# esp8266Board.net
KiCad netlist of a schematic drawn in EAGLE
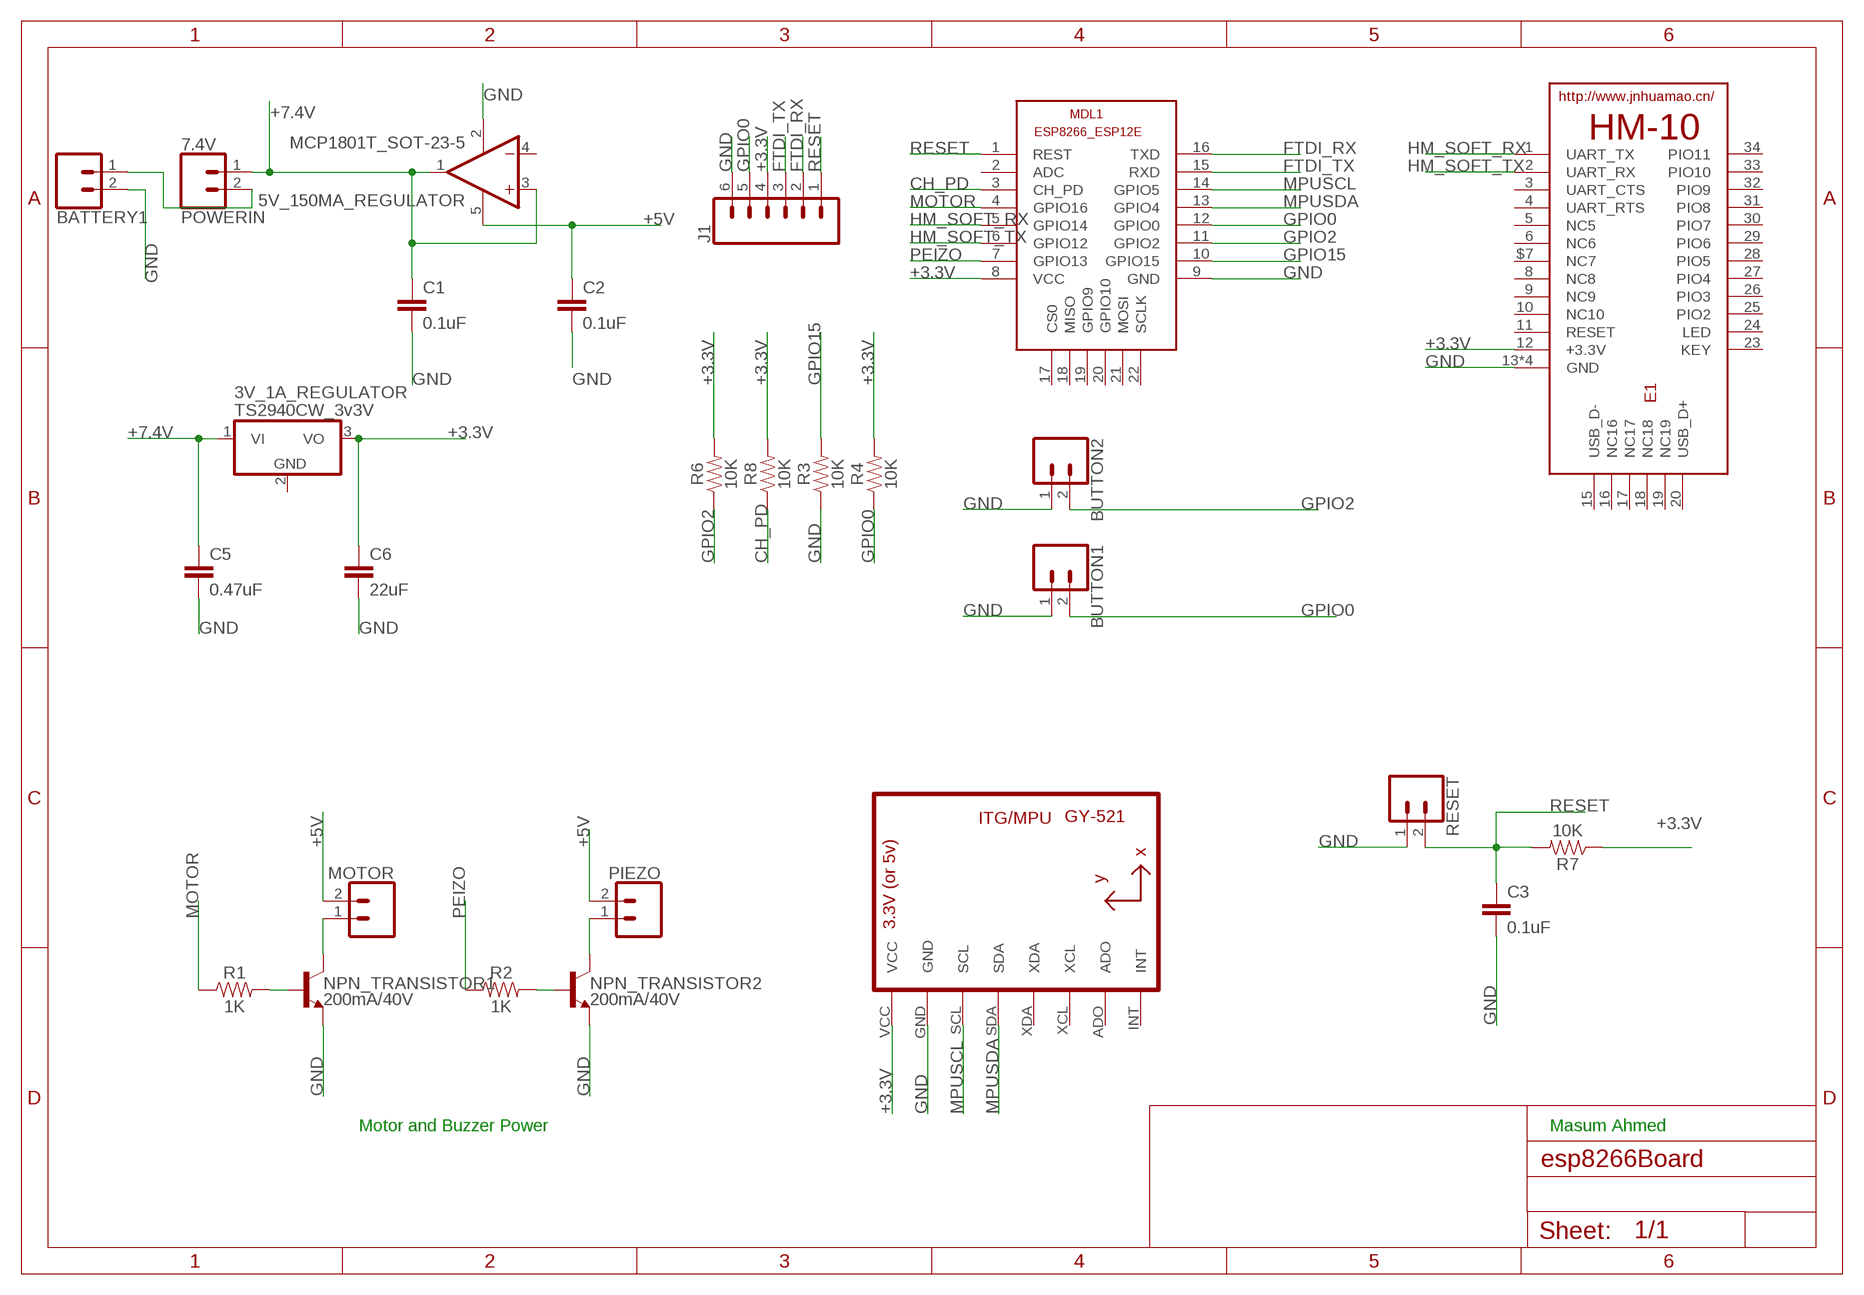
[diagram p0: schematic, sheet 1]

(export (version "E")
  (design (tool "Eeschema 10.0.6"))
  (components
    (comp (ref "3V_1A_REGULATOR")
      (value "TS2940CW_3v3V")
      (footprint "eagle-import:SOT223")
      (libsource (lib "eagle-import") (part "MCP1703DB"))
    )
    (comp (ref "5V_150MA_REGULATOR")
      (value "MCP1801T_SOT-23-5")
      (footprint "eagle-import:SOT23-5")
      (libsource (lib "eagle-import") (part "MCP601OT"))
    )
    (comp (ref "BATTERY1")
      (value "CONN_02")
      (footprint "eagle-import:1X02")
      (libsource (lib "eagle-import") (part "CONN_02"))
    )
    (comp (ref "BUTTON1")
      (value "CONN_02")
      (footprint "eagle-import:1X02")
      (libsource (lib "eagle-import") (part "CONN_02"))
    )
    (comp (ref "BUTTON2")
      (value "CONN_02")
      (footprint "eagle-import:1X02")
      (libsource (lib "eagle-import") (part "CONN_02"))
    )
    (comp (ref "C1")
      (value "0.1uF")
      (footprint "eagle-import:0805")
      (libsource (lib "eagle-import") (part "1.0UF-0805-25V-10%"))
    )
    (comp (ref "C2")
      (value "0.1uF")
      (footprint "eagle-import:0805")
      (libsource (lib "eagle-import") (part "1.0UF-0805-25V-10%"))
    )
    (comp (ref "C3")
      (value "0.1uF")
      (footprint "eagle-import:0805")
      (libsource (lib "eagle-import") (part "1.0UF-0805-25V-10%"))
    )
    (comp (ref "C5")
      (value "0.47uF")
      (footprint "eagle-import:CAP-PTH-SMALL-KIT")
      (libsource (lib "eagle-import") (part "0.1UF-KIT-EZ-50V-20%"))
    )
    (comp (ref "C6")
      (value "22uF")
      (footprint "eagle-import:CAP-PTH-SMALL-KIT")
      (libsource (lib "eagle-import") (part "0.1UF-KIT-EZ-50V-20%"))
    )
    (comp (ref "E1")
      (value "HM-10-BOARD")
      (footprint "eagle-import:26.9X13X2.2_BOARD")
      (libsource (lib "eagle-import") (part "HM-10-BOARD"))
    )
    (comp (ref "J1")
      (value "CONN_06SILK_FEMALE_PTH")
      (footprint "eagle-import:1X06")
      (libsource (lib "eagle-import") (part "CONN_06SILK_FEMALE_PTH"))
    )
    (comp (ref "MDL1")
      (value "ESP8266-12EESP8266-ESP12E")
      (footprint "eagle-import:ESP8266-ESP12E")
      (libsource (lib "eagle-import") (part "ESP8266-12EESP8266-ESP12E"))
    )
    (comp (ref "MOTOR")
      (value "CONN_02")
      (footprint "eagle-import:1X02")
      (libsource (lib "eagle-import") (part "CONN_02"))
    )
    (comp (ref "NPN_TRANSISTOR1")
      (value "200mA/40V")
      (footprint "eagle-import:TO-92")
      (libsource (lib "eagle-import") (part "TRANS_NPN-2N3904"))
    )
    (comp (ref "NPN_TRANSISTOR2")
      (value "200mA/40V")
      (footprint "eagle-import:TO-92")
      (libsource (lib "eagle-import") (part "TRANS_NPN-2N3904"))
    )
    (comp (ref "PIEZO")
      (value "CONN_02")
      (footprint "eagle-import:1X02")
      (libsource (lib "eagle-import") (part "CONN_02"))
    )
    (comp (ref "POWERIN")
      (value "7.4V")
      (footprint "eagle-import:1X02")
      (libsource (lib "eagle-import") (part "CONN_02"))
    )
    (comp (ref "R1")
      (value "1K")
      (footprint "eagle-import:0805")
      (libsource (lib "eagle-import") (part "0.22OHM-0805-1/4W-1%"))
    )
    (comp (ref "R2")
      (value "1K")
      (footprint "eagle-import:0805")
      (libsource (lib "eagle-import") (part "0.22OHM-0805-1/4W-1%"))
    )
    (comp (ref "R3")
      (value "10K")
      (footprint "eagle-import:0805")
      (libsource (lib "eagle-import") (part "0.22OHM-0805-1/4W-1%"))
    )
    (comp (ref "R4")
      (value "10K")
      (footprint "eagle-import:0805")
      (libsource (lib "eagle-import") (part "0.22OHM-0805-1/4W-1%"))
    )
    (comp (ref "R6")
      (value "10K")
      (footprint "eagle-import:0805")
      (libsource (lib "eagle-import") (part "0.22OHM-0805-1/4W-1%"))
    )
    (comp (ref "R7")
      (value "10K")
      (footprint "eagle-import:0805")
      (libsource (lib "eagle-import") (part "0.22OHM-0805-1/4W-1%"))
    )
    (comp (ref "R8")
      (value "10K")
      (footprint "eagle-import:0805")
      (libsource (lib "eagle-import") (part "0.22OHM-0805-1/4W-1%"))
    )
    (comp (ref "RESET")
      (value "CONN_02")
      (footprint "eagle-import:1X02")
      (libsource (lib "eagle-import") (part "CONN_02"))
    )
    (comp (ref "U1")
      (value "GY-521MPU6050")
      (footprint "eagle-import:GY-521")
      (libsource (lib "eagle-import") (part "GY-521MPU6050"))
    )
  )
  (nets
    (net (code "1") (name "/+3.3V") (class "Default")
      (node (ref "3V_1A_REGULATOR") (pin "3") (pinfunction "VO_3") (pintype "passive"))
      (node (ref "C6") (pin "1") (pinfunction "1_1") (pintype "passive"))
      (node (ref "E1") (pin "12") (pinfunction "+3.3V_12") (pintype "bidirectional"))
      (node (ref "J1") (pin "4") (pinfunction "4_4") (pintype "passive"))
      (node (ref "MDL1") (pin "8") (pinfunction "VCC_8") (pintype "bidirectional"))
      (node (ref "R4") (pin "2") (pinfunction "2_2") (pintype "passive"))
      (node (ref "R6") (pin "2") (pinfunction "2_2") (pintype "passive"))
      (node (ref "R7") (pin "1") (pinfunction "1_1") (pintype "passive"))
      (node (ref "R8") (pin "2") (pinfunction "2_2") (pintype "passive"))
      (node (ref "U1") (pin "VCC") (pinfunction "VCC_VCC") (pintype "bidirectional"))
    )
    (net (code "2") (name "/+5V") (class "Default")
      (node (ref "5V_150MA_REGULATOR") (pin "5") (pinfunction "V+_5") (pintype "power_in"))
      (node (ref "C2") (pin "1") (pinfunction "1_1") (pintype "passive"))
      (node (ref "MOTOR") (pin "2") (pinfunction "2_2") (pintype "passive"))
      (node (ref "PIEZO") (pin "2") (pinfunction "2_2") (pintype "passive"))
    )
    (net (code "3") (name "/+7.4V") (class "Default")
      (node (ref "3V_1A_REGULATOR") (pin "1") (pinfunction "VI_1") (pintype "input"))
      (node (ref "5V_150MA_REGULATOR") (pin "1") (pinfunction "OUT_1") (pintype "output"))
      (node (ref "5V_150MA_REGULATOR") (pin "3") (pinfunction "+IN_3") (pintype "input"))
      (node (ref "C1") (pin "1") (pinfunction "1_1") (pintype "passive"))
      (node (ref "C5") (pin "1") (pinfunction "1_1") (pintype "passive"))
      (node (ref "POWERIN") (pin "1") (pinfunction "1_1") (pintype "passive"))
    )
    (net (code "4") (name "/CH_PD") (class "Default")
      (node (ref "MDL1") (pin "3") (pinfunction "CH_PD_3") (pintype "bidirectional"))
      (node (ref "R8") (pin "1") (pinfunction "1_1") (pintype "passive"))
    )
    (net (code "5") (name "/FTDI_RX") (class "Default")
      (node (ref "J1") (pin "2") (pinfunction "2_2") (pintype "passive"))
      (node (ref "MDL1") (pin "16") (pinfunction "TXD_16") (pintype "bidirectional"))
    )
    (net (code "6") (name "/FTDI_TX") (class "Default")
      (node (ref "J1") (pin "3") (pinfunction "3_3") (pintype "passive"))
      (node (ref "MDL1") (pin "15") (pinfunction "RXD_15") (pintype "bidirectional"))
    )
    (net (code "7") (name "/GND") (class "Default")
      (node (ref "5V_150MA_REGULATOR") (pin "2") (pinfunction "V-_2") (pintype "power_in"))
      (node (ref "BATTERY1") (pin "2") (pinfunction "2_2") (pintype "passive"))
      (node (ref "BUTTON1") (pin "1") (pinfunction "1_1") (pintype "passive"))
      (node (ref "BUTTON2") (pin "1") (pinfunction "1_1") (pintype "passive"))
      (node (ref "C1") (pin "2") (pinfunction "2_2") (pintype "passive"))
      (node (ref "C2") (pin "2") (pinfunction "2_2") (pintype "passive"))
      (node (ref "C3") (pin "2") (pinfunction "2_2") (pintype "passive"))
      (node (ref "C5") (pin "2") (pinfunction "2_2") (pintype "passive"))
      (node (ref "C6") (pin "2") (pinfunction "2_2") (pintype "passive"))
      (node (ref "E1") (pin "13") (pinfunction "GND_13") (pintype "bidirectional"))
      (node (ref "E1") (pin "14") (pinfunction "GND_14") (pintype "bidirectional"))
      (node (ref "E1") (pin "21") (pinfunction "GND_21") (pintype "bidirectional"))
      (node (ref "E1") (pin "22") (pinfunction "GND_22") (pintype "bidirectional"))
      (node (ref "J1") (pin "6") (pinfunction "6_6") (pintype "passive"))
      (node (ref "MDL1") (pin "9") (pinfunction "GND_9") (pintype "bidirectional"))
      (node (ref "NPN_TRANSISTOR1") (pin "1") (pinfunction "E_1") (pintype "passive"))
      (node (ref "NPN_TRANSISTOR2") (pin "1") (pinfunction "E_1") (pintype "passive"))
      (node (ref "R3") (pin "1") (pinfunction "1_1") (pintype "passive"))
      (node (ref "RESET") (pin "1") (pinfunction "1_1") (pintype "passive"))
      (node (ref "U1") (pin "GND") (pinfunction "GND_GND") (pintype "bidirectional"))
    )
    (net (code "8") (name "/GPIO0") (class "Default")
      (node (ref "BUTTON1") (pin "2") (pinfunction "2_2") (pintype "passive"))
      (node (ref "J1") (pin "5") (pinfunction "5_5") (pintype "passive"))
      (node (ref "MDL1") (pin "12") (pinfunction "GPIO0_12") (pintype "bidirectional"))
      (node (ref "R4") (pin "1") (pinfunction "1_1") (pintype "passive"))
    )
    (net (code "9") (name "/GPIO2") (class "Default")
      (node (ref "BUTTON2") (pin "2") (pinfunction "2_2") (pintype "passive"))
      (node (ref "MDL1") (pin "11") (pinfunction "GPIO2_11") (pintype "bidirectional"))
      (node (ref "R6") (pin "1") (pinfunction "1_1") (pintype "passive"))
    )
    (net (code "10") (name "/GPIO15") (class "Default")
      (node (ref "MDL1") (pin "10") (pinfunction "GPIO15_10") (pintype "bidirectional"))
      (node (ref "R3") (pin "2") (pinfunction "2_2") (pintype "passive"))
    )
    (net (code "11") (name "/HM_SOFT_RX") (class "Default")
      (node (ref "E1") (pin "1") (pinfunction "UART_TX_1") (pintype "bidirectional"))
      (node (ref "MDL1") (pin "5") (pinfunction "GPIO14_5") (pintype "bidirectional"))
    )
    (net (code "12") (name "/HM_SOFT_TX") (class "Default")
      (node (ref "E1") (pin "2") (pinfunction "UART_RX_2") (pintype "bidirectional"))
      (node (ref "MDL1") (pin "6") (pinfunction "GPIO12_6") (pintype "bidirectional"))
    )
    (net (code "13") (name "/MOTOR") (class "Default")
      (node (ref "MDL1") (pin "4") (pinfunction "GPIO16_4") (pintype "bidirectional"))
      (node (ref "R1") (pin "1") (pinfunction "1_1") (pintype "passive"))
    )
    (net (code "14") (name "/MPUSCL") (class "Default")
      (node (ref "MDL1") (pin "14") (pinfunction "GPIO5_14") (pintype "bidirectional"))
      (node (ref "U1") (pin "SCL") (pinfunction "SCL_SCL") (pintype "bidirectional"))
    )
    (net (code "15") (name "/MPUSDA") (class "Default")
      (node (ref "MDL1") (pin "13") (pinfunction "GPIO4_13") (pintype "bidirectional"))
      (node (ref "U1") (pin "SDA") (pinfunction "SDA_SDA") (pintype "bidirectional"))
    )
    (net (code "16") (name "/PEIZO") (class "Default")
      (node (ref "MDL1") (pin "7") (pinfunction "GPIO13_7") (pintype "bidirectional"))
      (node (ref "R2") (pin "1") (pinfunction "1_1") (pintype "passive"))
    )
    (net (code "17") (name "/RESET") (class "Default")
      (node (ref "C3") (pin "1") (pinfunction "1_1") (pintype "passive"))
      (node (ref "J1") (pin "1") (pinfunction "1_1") (pintype "passive"))
      (node (ref "MDL1") (pin "1") (pinfunction "REST_1") (pintype "bidirectional"))
      (node (ref "R7") (pin "2") (pinfunction "2_2") (pintype "passive"))
      (node (ref "RESET") (pin "2") (pinfunction "2_2") (pintype "passive"))
    )
    (net (code "18") (name "Net-(BATTERY1-Pad1)") (class "Default")
      (node (ref "BATTERY1") (pin "1") (pinfunction "1_1") (pintype "passive"))
      (node (ref "POWERIN") (pin "2") (pinfunction "2_2") (pintype "passive"))
    )
    (net (code "19") (name "Net-(NPN_TRANSISTOR1-B)") (class "Default")
      (node (ref "NPN_TRANSISTOR1") (pin "2") (pinfunction "B_2") (pintype "passive"))
      (node (ref "R1") (pin "2") (pinfunction "2_2") (pintype "passive"))
    )
    (net (code "20") (name "Net-(NPN_TRANSISTOR1-C)") (class "Default")
      (node (ref "MOTOR") (pin "1") (pinfunction "1_1") (pintype "passive"))
      (node (ref "NPN_TRANSISTOR1") (pin "3") (pinfunction "C_3") (pintype "passive"))
    )
    (net (code "21") (name "Net-(NPN_TRANSISTOR2-B)") (class "Default")
      (node (ref "NPN_TRANSISTOR2") (pin "2") (pinfunction "B_2") (pintype "passive"))
      (node (ref "R2") (pin "2") (pinfunction "2_2") (pintype "passive"))
    )
    (net (code "22") (name "Net-(NPN_TRANSISTOR2-C)") (class "Default")
      (node (ref "NPN_TRANSISTOR2") (pin "3") (pinfunction "C_3") (pintype "passive"))
      (node (ref "PIEZO") (pin "1") (pinfunction "1_1") (pintype "passive"))
    )
    (net (code "23") (name "unconnected-(3V_1A_REGULATOR-GND-Pad2)") (class "Default")
      (node (ref "3V_1A_REGULATOR") (pin "2") (pinfunction "GND_2") (pintype "passive"))
    )
    (net (code "24") (name "unconnected-(5V_150MA_REGULATOR--IN-Pad4)") (class "Default")
      (node (ref "5V_150MA_REGULATOR") (pin "4") (pinfunction "-IN_4") (pintype "input"))
    )
    (net (code "25") (name "unconnected-(E1-KEY-Pad23)") (class "Default")
      (node (ref "E1") (pin "23") (pinfunction "KEY_23") (pintype "bidirectional"))
    )
    (net (code "26") (name "unconnected-(E1-LED-Pad24)") (class "Default")
      (node (ref "E1") (pin "24") (pinfunction "LED_24") (pintype "bidirectional"))
    )
    (net (code "27") (name "unconnected-(E1-NC5-Pad5)") (class "Default")
      (node (ref "E1") (pin "5") (pinfunction "NC5_5") (pintype "bidirectional"))
    )
    (net (code "28") (name "unconnected-(E1-NC6-Pad6)") (class "Default")
      (node (ref "E1") (pin "6") (pinfunction "NC6_6") (pintype "bidirectional"))
    )
    (net (code "29") (name "unconnected-(E1-NC7-Pad$7)") (class "Default")
      (node (ref "E1") (pin "$7") (pinfunction "NC7_$7") (pintype "bidirectional"))
    )
    (net (code "30") (name "unconnected-(E1-NC8-Pad8)") (class "Default")
      (node (ref "E1") (pin "8") (pinfunction "NC8_8") (pintype "bidirectional"))
    )
    (net (code "31") (name "unconnected-(E1-NC9-Pad9)") (class "Default")
      (node (ref "E1") (pin "9") (pinfunction "NC9_9") (pintype "bidirectional"))
    )
    (net (code "32") (name "unconnected-(E1-NC10-Pad10)") (class "Default")
      (node (ref "E1") (pin "10") (pinfunction "NC10_10") (pintype "bidirectional"))
    )
    (net (code "33") (name "unconnected-(E1-NC16-Pad16)") (class "Default")
      (node (ref "E1") (pin "16") (pinfunction "NC16_16") (pintype "bidirectional"))
    )
    (net (code "34") (name "unconnected-(E1-NC17-Pad17)") (class "Default")
      (node (ref "E1") (pin "17") (pinfunction "NC17_17") (pintype "bidirectional"))
    )
    (net (code "35") (name "unconnected-(E1-NC18-Pad18)") (class "Default")
      (node (ref "E1") (pin "18") (pinfunction "NC18_18") (pintype "bidirectional"))
    )
    (net (code "36") (name "unconnected-(E1-NC19-Pad19)") (class "Default")
      (node (ref "E1") (pin "19") (pinfunction "NC19_19") (pintype "bidirectional"))
    )
    (net (code "37") (name "unconnected-(E1-PIO2-Pad25)") (class "Default")
      (node (ref "E1") (pin "25") (pinfunction "PIO2_25") (pintype "bidirectional"))
    )
    (net (code "38") (name "unconnected-(E1-PIO3-Pad26)") (class "Default")
      (node (ref "E1") (pin "26") (pinfunction "PIO3_26") (pintype "bidirectional"))
    )
    (net (code "39") (name "unconnected-(E1-PIO4-Pad27)") (class "Default")
      (node (ref "E1") (pin "27") (pinfunction "PIO4_27") (pintype "bidirectional"))
    )
    (net (code "40") (name "unconnected-(E1-PIO5-Pad28)") (class "Default")
      (node (ref "E1") (pin "28") (pinfunction "PIO5_28") (pintype "bidirectional"))
    )
    (net (code "41") (name "unconnected-(E1-PIO6-Pad29)") (class "Default")
      (node (ref "E1") (pin "29") (pinfunction "PIO6_29") (pintype "bidirectional"))
    )
    (net (code "42") (name "unconnected-(E1-PIO7-Pad30)") (class "Default")
      (node (ref "E1") (pin "30") (pinfunction "PIO7_30") (pintype "bidirectional"))
    )
    (net (code "43") (name "unconnected-(E1-PIO8-Pad31)") (class "Default")
      (node (ref "E1") (pin "31") (pinfunction "PIO8_31") (pintype "bidirectional"))
    )
    (net (code "44") (name "unconnected-(E1-PIO9-Pad32)") (class "Default")
      (node (ref "E1") (pin "32") (pinfunction "PIO9_32") (pintype "bidirectional"))
    )
    (net (code "45") (name "unconnected-(E1-PIO10-Pad33)") (class "Default")
      (node (ref "E1") (pin "33") (pinfunction "PIO10_33") (pintype "bidirectional"))
    )
    (net (code "46") (name "unconnected-(E1-PIO11-Pad34)") (class "Default")
      (node (ref "E1") (pin "34") (pinfunction "PIO11_34") (pintype "bidirectional"))
    )
    (net (code "47") (name "unconnected-(E1-RESET-Pad11)") (class "Default")
      (node (ref "E1") (pin "11") (pinfunction "RESET_11") (pintype "bidirectional"))
    )
    (net (code "48") (name "unconnected-(E1-UART_CTS-Pad3)") (class "Default")
      (node (ref "E1") (pin "3") (pinfunction "UART_CTS_3") (pintype "bidirectional"))
    )
    (net (code "49") (name "unconnected-(E1-UART_RTS-Pad4)") (class "Default")
      (node (ref "E1") (pin "4") (pinfunction "UART_RTS_4") (pintype "bidirectional"))
    )
    (net (code "50") (name "unconnected-(E1-USB_D+-Pad20)") (class "Default")
      (node (ref "E1") (pin "20") (pinfunction "USB_D+_20") (pintype "bidirectional"))
    )
    (net (code "51") (name "unconnected-(E1-USB_D--Pad15)") (class "Default")
      (node (ref "E1") (pin "15") (pinfunction "USB_D-_15") (pintype "bidirectional"))
    )
    (net (code "52") (name "unconnected-(MDL1-ADC-Pad2)") (class "Default")
      (node (ref "MDL1") (pin "2") (pinfunction "ADC_2") (pintype "bidirectional"))
    )
    (net (code "53") (name "unconnected-(MDL1-CS0-Pad17)") (class "Default")
      (node (ref "MDL1") (pin "17") (pinfunction "CS0_17") (pintype "bidirectional"))
    )
    (net (code "54") (name "unconnected-(MDL1-GPIO9-Pad19)") (class "Default")
      (node (ref "MDL1") (pin "19") (pinfunction "GPIO9_19") (pintype "bidirectional"))
    )
    (net (code "55") (name "unconnected-(MDL1-GPIO10-Pad20)") (class "Default")
      (node (ref "MDL1") (pin "20") (pinfunction "GPIO10_20") (pintype "bidirectional"))
    )
    (net (code "56") (name "unconnected-(MDL1-MISO-Pad18)") (class "Default")
      (node (ref "MDL1") (pin "18") (pinfunction "MISO_18") (pintype "bidirectional"))
    )
    (net (code "57") (name "unconnected-(MDL1-MOSI-Pad21)") (class "Default")
      (node (ref "MDL1") (pin "21") (pinfunction "MOSI_21") (pintype "bidirectional"))
    )
    (net (code "58") (name "unconnected-(MDL1-SCLK-Pad22)") (class "Default")
      (node (ref "MDL1") (pin "22") (pinfunction "SCLK_22") (pintype "bidirectional"))
    )
    (net (code "59") (name "unconnected-(U1-PadADO)") (class "Default")
      (node (ref "U1") (pin "ADO") (pinfunction "ADO_ADO") (pintype "bidirectional"))
    )
    (net (code "60") (name "unconnected-(U1-PadINT)") (class "Default")
      (node (ref "U1") (pin "INT") (pinfunction "INT_INT") (pintype "bidirectional"))
    )
    (net (code "61") (name "unconnected-(U1-PadXCL)") (class "Default")
      (node (ref "U1") (pin "XCL") (pinfunction "XCL_XCL") (pintype "bidirectional"))
    )
    (net (code "62") (name "unconnected-(U1-PadXDA)") (class "Default")
      (node (ref "U1") (pin "XDA") (pinfunction "XDA_XDA") (pintype "bidirectional"))
    )
  )
)
